# design.net
KiCad netlist of a schematic drawn in Altium Designer
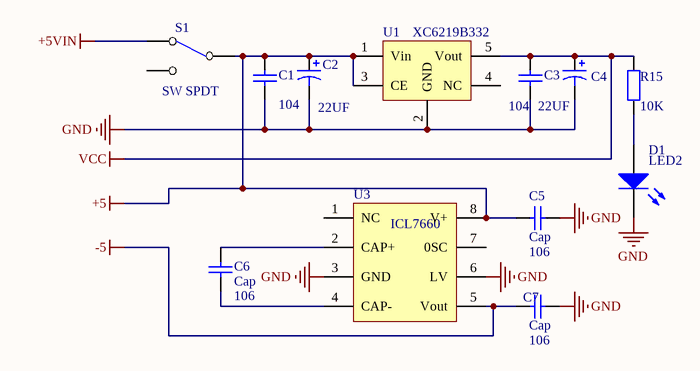
[diagram p0: 电源电路.SchDoc]

(export (version "E")
  (design (tool "Eeschema 10.0.6"))
  (components
    (comp (ref "C1")
      (value "104")
      (footprint "C0805")
      (description "Capacitor")
      (fields (field (name "Comment") "Cap") (field (name "PUBLISHER") "Altium Limited"))
      (libsource (lib "基于SMT32的DDS信号源原理图库") (part "Cap"))
    )
    (comp (ref "C2")
      (value "22UF")
      (footprint "C1210_N")
      (description "Polarized Capacitor (Radial)")
      (fields (field (name "Comment") "Cap Pol1") (field (name "PUBLISHER") "Altium Limited"))
      (libsource (lib "基于SMT32的DDS信号源原理图库") (part "Cap Pol1"))
    )
    (comp (ref "C3")
      (value "104")
      (footprint "C0805")
      (description "Capacitor")
      (fields (field (name "Comment") "Cap") (field (name "PUBLISHER") "Altium Limited"))
      (libsource (lib "基于SMT32的DDS信号源原理图库") (part "Cap"))
    )
    (comp (ref "C4")
      (value "22UF")
      (footprint "C1210_N")
      (description "Polarized Capacitor (Radial)")
      (fields (field (name "Comment") "Cap Pol1") (field (name "PUBLISHER") "Altium Limited"))
      (libsource (lib "基于SMT32的DDS信号源原理图库") (part "Cap Pol1"))
    )
    (comp (ref "C5")
      (value "Cap")
      (footprint "C0805")
      (description "Capacitor")
      (fields (field (name "ALTIUM_VALUE") "106") (field (name "PUBLISHER") "Altium Limited"))
      (libsource (lib "基于SMT32的DDS信号源原理图库") (part "Cap"))
    )
    (comp (ref "C6")
      (value "Cap")
      (footprint "C0805")
      (description "Capacitor")
      (fields (field (name "ALTIUM_VALUE") "106") (field (name "PUBLISHER") "Altium Limited"))
      (libsource (lib "基于SMT32的DDS信号源原理图库") (part "Cap"))
    )
    (comp (ref "C7")
      (value "Cap")
      (footprint "C0805")
      (description "Capacitor")
      (fields (field (name "ALTIUM_VALUE") "106") (field (name "PUBLISHER") "Altium Limited"))
      (libsource (lib "基于SMT32的DDS信号源原理图库") (part "Cap"))
    )
    (comp (ref "D1")
      (value "LED2")
      (footprint "D0805+")
      (description "Typical RED, GREEN, YELLOW, AMBER GaAs LED")
      (fields (field (name "PUBLISHER") "Altium Limited"))
      (libsource (lib "基于SMT32的DDS信号源原理图库") (part "LED2"))
    )
    (comp (ref "R15")
      (value "10K")
      (footprint "6-0805_N")
      (description "Resistor")
      (fields (field (name "Comment") "Res2") (field (name "PUBLISHER") "Altium Limited"))
      (libsource (lib "基于SMT32的DDS信号源原理图库") (part "Res2"))
    )
    (comp (ref "S1")
      (value "SW SPDT")
      (footprint "SW-SPDT-7P")
      (libsource (lib "基于SMT32的DDS信号源原理图库") (part "SW SPDT"))
    )
    (comp (ref "U1")
      (value "XC6219B332")
      (footprint "SOT23-5L")
      (libsource (lib "基于SMT32的DDS信号源原理图库") (part "XC6219"))
    )
    (comp (ref "U3")
      (value "ICL7660")
      (footprint "SO8_N")
      (libsource (lib "基于SMT32的DDS信号源原理图库") (part "ICL7660"))
    )
  )
  (nets
    (net (code "1") (name "+5") (class "Default")
      (node (ref "C1") (pin "2") (pinfunction "2_2") (pintype "passive"))
      (node (ref "C2") (pin "1") (pinfunction "1_1") (pintype "passive"))
      (node (ref "C5") (pin "2") (pinfunction "2_2") (pintype "passive"))
      (node (ref "S1") (pin "2") (pinfunction "COMMON_2") (pintype "passive"))
      (node (ref "U1") (pin "1") (pinfunction "Vin_1") (pintype "passive"))
      (node (ref "U1") (pin "3") (pinfunction "CE_3") (pintype "passive"))
      (node (ref "U3") (pin "8") (pinfunction "V+_8") (pintype "passive"))
    )
    (net (code "2") (name "+5VIN") (class "Default")
      (node (ref "S1") (pin "1") (pinfunction "NC_1") (pintype "passive"))
    )
    (net (code "3") (name "-5") (class "Default")
      (node (ref "C7") (pin "2") (pinfunction "2_2") (pintype "passive"))
      (node (ref "U3") (pin "5") (pinfunction "Vout_5") (pintype "passive"))
    )
    (net (code "4") (name "GND") (class "Default")
      (node (ref "C1") (pin "1") (pinfunction "1_1") (pintype "passive"))
      (node (ref "C2") (pin "2") (pinfunction "2_2") (pintype "passive"))
      (node (ref "C3") (pin "1") (pinfunction "1_1") (pintype "passive"))
      (node (ref "C4") (pin "2") (pinfunction "2_2") (pintype "passive"))
      (node (ref "C5") (pin "1") (pinfunction "1_1") (pintype "passive"))
      (node (ref "C7") (pin "1") (pinfunction "1_1") (pintype "passive"))
      (node (ref "D1") (pin "K") (pinfunction "K_K") (pintype "passive"))
      (node (ref "U1") (pin "2") (pinfunction "GND_2") (pintype "power_in"))
      (node (ref "U3") (pin "3") (pinfunction "GND_3") (pintype "passive"))
      (node (ref "U3") (pin "6") (pinfunction "LV_6") (pintype "passive"))
    )
    (net (code "5") (name "Net-(D1-PadA)") (class "Default")
      (node (ref "D1") (pin "A") (pinfunction "A_A") (pintype "passive"))
      (node (ref "R15") (pin "1") (pinfunction "1_1") (pintype "passive"))
    )
    (net (code "6") (name "Net-(U3-CAP+)") (class "Default")
      (node (ref "C6") (pin "1") (pinfunction "1_1") (pintype "passive"))
      (node (ref "U3") (pin "2") (pinfunction "CAP+_2") (pintype "passive"))
    )
    (net (code "7") (name "Net-(U3-CAP-)") (class "Default")
      (node (ref "C6") (pin "2") (pinfunction "2_2") (pintype "passive"))
      (node (ref "U3") (pin "4") (pinfunction "CAP-_4") (pintype "passive"))
    )
    (net (code "8") (name "VCC") (class "Default")
      (node (ref "C3") (pin "2") (pinfunction "2_2") (pintype "passive"))
      (node (ref "C4") (pin "1") (pinfunction "1_1") (pintype "passive"))
      (node (ref "R15") (pin "2") (pinfunction "2_2") (pintype "passive"))
      (node (ref "U1") (pin "5") (pinfunction "Vout_5") (pintype "passive"))
    )
    (net (code "9") (name "unconnected-(S1-NO-Pad3)") (class "Default")
      (node (ref "S1") (pin "3") (pinfunction "NO_3") (pintype "passive"))
    )
    (net (code "10") (name "unconnected-(U1-NC-Pad4)") (class "Default")
      (node (ref "U1") (pin "4") (pinfunction "NC_4") (pintype "passive"))
    )
    (net (code "11") (name "unconnected-(U3-0SC-Pad7)") (class "Default")
      (node (ref "U3") (pin "7") (pinfunction "0SC_7") (pintype "passive"))
    )
    (net (code "12") (name "unconnected-(U3-NC-Pad1)") (class "Default")
      (node (ref "U3") (pin "1") (pinfunction "NC_1") (pintype "passive"))
    )
  )
)
